# zerod.net
KiCad netlist of a schematic drawn in EAGLE
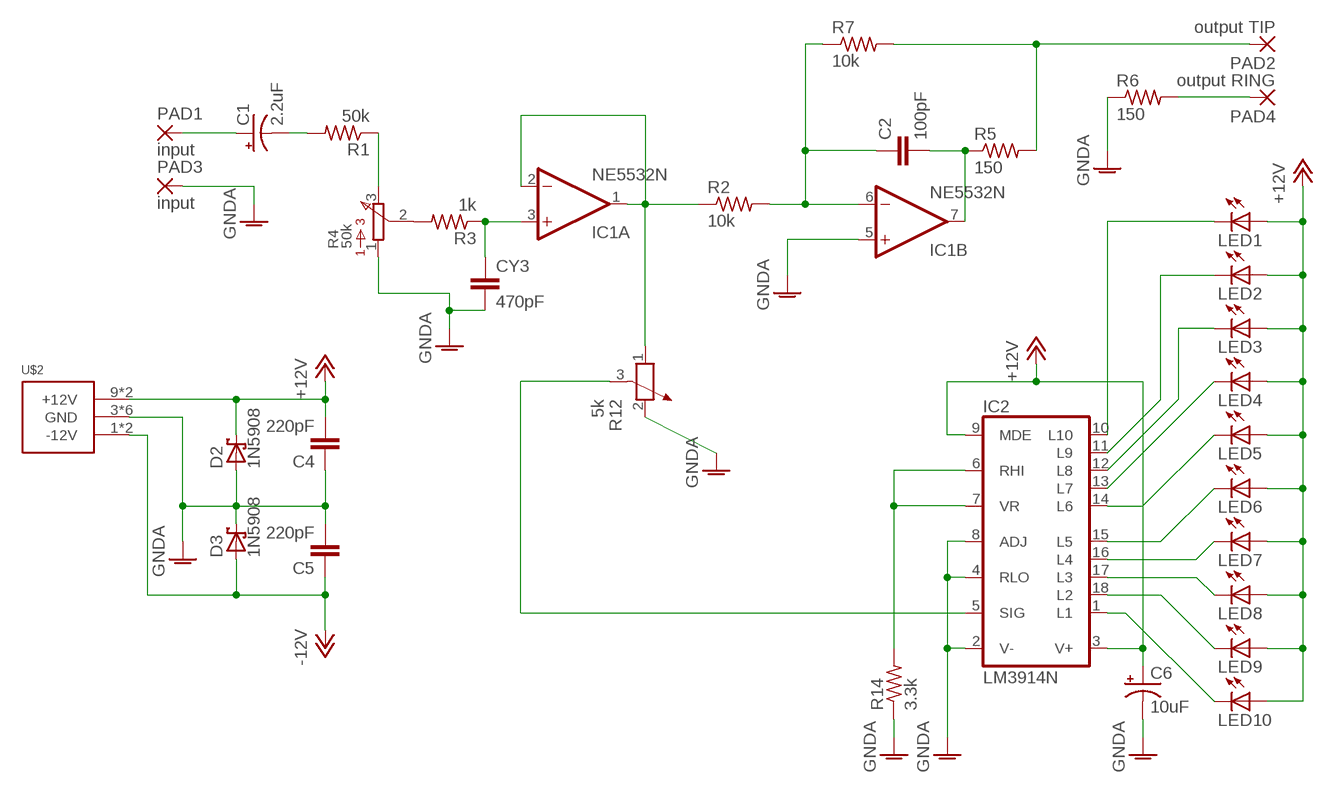
[diagram p0: schematic, sheet 1]

(export (version "E")
  (design (tool "Eeschema 10.0.6"))
  (components
    (comp (ref "C1")
      (value "2.2uF")
      (footprint "eagle-import:E15-6")
      (libsource (lib "eagle-import") (part "CPOL-USE15-6AXIAL"))
    )
    (comp (ref "C2")
      (value "100pF")
      (footprint "eagle-import:C2.5-6")
      (libsource (lib "eagle-import") (part "C2.5/6"))
    )
    (comp (ref "C4")
      (value "220pF")
      (footprint "eagle-import:C025-024X044")
      (libsource (lib "eagle-import") (part "C-EU025-024X044"))
    )
    (comp (ref "C5")
      (value "220pF")
      (footprint "eagle-import:C025-024X044")
      (libsource (lib "eagle-import") (part "C-EU025-024X044"))
    )
    (comp (ref "C6")
      (value "10uF")
      (footprint "eagle-import:E1,8-4")
      (libsource (lib "eagle-import") (part "CPOL-USE1.8-4"))
    )
    (comp (ref "CY3")
      (value "470pF")
      (footprint "eagle-import:YC7B5")
      (libsource (lib "eagle-import") (part "CYYC7B5"))
    )
    (comp (ref "D2")
      (value "1N5908")
      (footprint "eagle-import:C4111-15")
      (libsource (lib "eagle-import") (part "1N5908"))
    )
    (comp (ref "D3")
      (value "1N5908")
      (footprint "eagle-import:C4111-15")
      (libsource (lib "eagle-import") (part "1N5908"))
    )
    (comp (ref "IC1")
      (value "NE5532N")
      (footprint "eagle-import:DIL08")
      (libsource (lib "eagle-import") (part "NE5532N"))
    )
    (comp (ref "IC2")
      (value "LM3914N")
      (footprint "eagle-import:DIL18")
      (libsource (lib "eagle-import") (part "LM3914N"))
    )
    (comp (ref "LED1")
      (value "LED5MM")
      (footprint "eagle-import:LED5MM")
      (libsource (lib "eagle-import") (part "LED5MM"))
    )
    (comp (ref "LED2")
      (value "LED5MM")
      (footprint "eagle-import:LED5MM")
      (libsource (lib "eagle-import") (part "LED5MM"))
    )
    (comp (ref "LED3")
      (value "LED5MM")
      (footprint "eagle-import:LED5MM")
      (libsource (lib "eagle-import") (part "LED5MM"))
    )
    (comp (ref "LED4")
      (value "LED5MM")
      (footprint "eagle-import:LED5MM")
      (libsource (lib "eagle-import") (part "LED5MM"))
    )
    (comp (ref "LED5")
      (value "LED5MM")
      (footprint "eagle-import:LED5MM")
      (libsource (lib "eagle-import") (part "LED5MM"))
    )
    (comp (ref "LED6")
      (value "LED5MM")
      (footprint "eagle-import:LED5MM")
      (libsource (lib "eagle-import") (part "LED5MM"))
    )
    (comp (ref "LED7")
      (value "LED5MM")
      (footprint "eagle-import:LED5MM")
      (libsource (lib "eagle-import") (part "LED5MM"))
    )
    (comp (ref "LED8")
      (value "LED5MM")
      (footprint "eagle-import:LED5MM")
      (libsource (lib "eagle-import") (part "LED5MM"))
    )
    (comp (ref "LED9")
      (value "LED5MM")
      (footprint "eagle-import:LED5MM")
      (libsource (lib "eagle-import") (part "LED5MM"))
    )
    (comp (ref "LED10")
      (value "LED5MM")
      (footprint "eagle-import:LED5MM")
      (libsource (lib "eagle-import") (part "LED5MM"))
    )
    (comp (ref "PAD1")
      (value "input")
      (footprint "eagle-import:3,17_1,3")
      (libsource (lib "eagle-import") (part "3,17/1,3"))
    )
    (comp (ref "PAD2")
      (value "output TIP")
      (footprint "eagle-import:3,17_1,3")
      (libsource (lib "eagle-import") (part "3,17/1,3"))
    )
    (comp (ref "PAD3")
      (value "input")
      (footprint "eagle-import:3,17_1,3")
      (libsource (lib "eagle-import") (part "3,17/1,3"))
    )
    (comp (ref "PAD4")
      (value "output RING")
      (footprint "eagle-import:3,17_1,3")
      (libsource (lib "eagle-import") (part "3,17/1,3"))
    )
    (comp (ref "R1")
      (value "50k")
      (footprint "eagle-import:0207_10")
      (libsource (lib "eagle-import") (part "R-US_0207/10"))
    )
    (comp (ref "R2")
      (value "10k")
      (footprint "eagle-import:0207_10")
      (libsource (lib "eagle-import") (part "R-US_0207/10"))
    )
    (comp (ref "R3")
      (value "1k")
      (footprint "eagle-import:0207_10")
      (libsource (lib "eagle-import") (part "R-US_0207/10"))
    )
    (comp (ref "R4") (value "50k") (footprint "eagle-import:91") (libsource (lib "eagle-import") (part "91")))
    (comp (ref "R5")
      (value "150")
      (footprint "eagle-import:0207_10")
      (libsource (lib "eagle-import") (part "R-US_0207/10"))
    )
    (comp (ref "R6")
      (value "150")
      (footprint "eagle-import:0207_10")
      (libsource (lib "eagle-import") (part "R-US_0207/10"))
    )
    (comp (ref "R7")
      (value "10k")
      (footprint "eagle-import:0207_10")
      (libsource (lib "eagle-import") (part "R-US_0207/10"))
    )
    (comp (ref "R12")
      (value "5k")
      (footprint "eagle-import:PT-10S")
      (libsource (lib "eagle-import") (part "POTENTIOMETER_PT-10S"))
    )
    (comp (ref "R14")
      (value "3.3k")
      (footprint "eagle-import:0207_10")
      (libsource (lib "eagle-import") (part "R-US_0207/10"))
    )
    (comp (ref "U$2")
      (value "POWER_SIMPLE10")
      (footprint "eagle-import:POWER_10")
      (libsource (lib "eagle-import") (part "POWER_SIMPLE10"))
    )
  )
  (nets
    (net (code "1") (name "+12V") (class "Default")
      (node (ref "C4") (pin "2") (pinfunction "2_2") (pintype "passive"))
      (node (ref "C6") (pin "+") (pinfunction "+_+") (pintype "passive"))
      (node (ref "D2") (pin "C") (pinfunction "C_C") (pintype "passive"))
      (node (ref "IC2") (pin "3") (pinfunction "V+_3") (pintype "power_in"))
      (node (ref "IC2") (pin "9") (pinfunction "MDE_9") (pintype "input"))
      (node (ref "LED1") (pin "A") (pinfunction "A_A") (pintype "passive"))
      (node (ref "LED10") (pin "A") (pinfunction "A_A") (pintype "passive"))
      (node (ref "LED2") (pin "A") (pinfunction "A_A") (pintype "passive"))
      (node (ref "LED3") (pin "A") (pinfunction "A_A") (pintype "passive"))
      (node (ref "LED4") (pin "A") (pinfunction "A_A") (pintype "passive"))
      (node (ref "LED5") (pin "A") (pinfunction "A_A") (pintype "passive"))
      (node (ref "LED6") (pin "A") (pinfunction "A_A") (pintype "passive"))
      (node (ref "LED7") (pin "A") (pinfunction "A_A") (pintype "passive"))
      (node (ref "LED8") (pin "A") (pinfunction "A_A") (pintype "passive"))
      (node (ref "LED9") (pin "A") (pinfunction "A_A") (pintype "passive"))
      (node (ref "U$2") (pin "10") (pinfunction "+12V_10") (pintype "bidirectional"))
      (node (ref "U$2") (pin "9") (pinfunction "+12V_9") (pintype "bidirectional"))
    )
    (net (code "2") (name "-12V") (class "Default")
      (node (ref "C5") (pin "1") (pinfunction "1_1") (pintype "passive"))
      (node (ref "D3") (pin "A") (pinfunction "A_A") (pintype "passive"))
      (node (ref "U$2") (pin "1") (pinfunction "-12V_1") (pintype "bidirectional"))
      (node (ref "U$2") (pin "2") (pinfunction "-12V_2") (pintype "bidirectional"))
    )
    (net (code "3") (name "GNDA") (class "Default")
      (node (ref "C4") (pin "1") (pinfunction "1_1") (pintype "passive"))
      (node (ref "C5") (pin "2") (pinfunction "2_2") (pintype "passive"))
      (node (ref "C6") (pin "-") (pinfunction "-_-") (pintype "passive"))
      (node (ref "CY3") (pin "2") (pinfunction "2_2") (pintype "passive"))
      (node (ref "D2") (pin "A") (pinfunction "A_A") (pintype "passive"))
      (node (ref "D3") (pin "C") (pinfunction "C_C") (pintype "passive"))
      (node (ref "IC1") (pin "5") (pinfunction "+IN_5") (pintype "input"))
      (node (ref "IC2") (pin "2") (pinfunction "V-_2") (pintype "power_in"))
      (node (ref "IC2") (pin "4") (pinfunction "RLO_4") (pintype "input"))
      (node (ref "IC2") (pin "8") (pinfunction "ADJ_8") (pintype "input"))
      (node (ref "PAD3") (pin "1") (pinfunction "P_1") (pintype "passive"))
      (node (ref "R12") (pin "2") (pinfunction "2_2") (pintype "passive"))
      (node (ref "R14") (pin "1") (pinfunction "1_1") (pintype "passive"))
      (node (ref "R4") (pin "1") (pinfunction "1_1") (pintype "passive"))
      (node (ref "R6") (pin "1") (pinfunction "1_1") (pintype "passive"))
      (node (ref "U$2") (pin "3") (pinfunction "GND_3") (pintype "bidirectional"))
      (node (ref "U$2") (pin "4") (pinfunction "GND_4") (pintype "bidirectional"))
      (node (ref "U$2") (pin "5") (pinfunction "GND_5") (pintype "bidirectional"))
      (node (ref "U$2") (pin "6") (pinfunction "GND_6") (pintype "bidirectional"))
      (node (ref "U$2") (pin "7") (pinfunction "GND_7") (pintype "bidirectional"))
      (node (ref "U$2") (pin "8") (pinfunction "GND_8") (pintype "bidirectional"))
    )
    (net (code "4") (name "Net-(C1-Pad-)") (class "Default")
      (node (ref "C1") (pin "-") (pinfunction "-_-") (pintype "passive"))
      (node (ref "R1") (pin "2") (pinfunction "2_2") (pintype "passive"))
    )
    (net (code "5") (name "Net-(IC1A-+IN)") (class "Default")
      (node (ref "CY3") (pin "1") (pinfunction "1_1") (pintype "passive"))
      (node (ref "IC1") (pin "3") (pinfunction "+IN_3") (pintype "input"))
      (node (ref "R3") (pin "1") (pinfunction "1_1") (pintype "passive"))
    )
    (net (code "6") (name "Net-(IC1A--IN)") (class "Default")
      (node (ref "IC1") (pin "1") (pinfunction "OUT_1") (pintype "output"))
      (node (ref "IC1") (pin "2") (pinfunction "-IN_2") (pintype "input"))
      (node (ref "R12") (pin "1") (pinfunction "1_1") (pintype "passive"))
      (node (ref "R2") (pin "1") (pinfunction "1_1") (pintype "passive"))
    )
    (net (code "7") (name "Net-(IC1B--IN)") (class "Default")
      (node (ref "C2") (pin "1") (pinfunction "1_1") (pintype "passive"))
      (node (ref "IC1") (pin "6") (pinfunction "-IN_6") (pintype "input"))
      (node (ref "R2") (pin "2") (pinfunction "2_2") (pintype "passive"))
      (node (ref "R7") (pin "1") (pinfunction "1_1") (pintype "passive"))
    )
    (net (code "8") (name "Net-(IC1B-OUT)") (class "Default")
      (node (ref "C2") (pin "2") (pinfunction "2_2") (pintype "passive"))
      (node (ref "IC1") (pin "7") (pinfunction "OUT_7") (pintype "output"))
      (node (ref "R5") (pin "1") (pinfunction "1_1") (pintype "passive"))
    )
    (net (code "9") (name "Net-(IC2-L1)") (class "Default")
      (node (ref "IC2") (pin "1") (pinfunction "L1_1") (pintype "output"))
      (node (ref "LED10") (pin "K") (pinfunction "C_K") (pintype "passive"))
    )
    (net (code "10") (name "Net-(IC2-L2)") (class "Default")
      (node (ref "IC2") (pin "18") (pinfunction "L2_18") (pintype "output"))
      (node (ref "LED9") (pin "K") (pinfunction "C_K") (pintype "passive"))
    )
    (net (code "11") (name "Net-(IC2-L3)") (class "Default")
      (node (ref "IC2") (pin "17") (pinfunction "L3_17") (pintype "output"))
      (node (ref "LED8") (pin "K") (pinfunction "C_K") (pintype "passive"))
    )
    (net (code "12") (name "Net-(IC2-L4)") (class "Default")
      (node (ref "IC2") (pin "16") (pinfunction "L4_16") (pintype "output"))
      (node (ref "LED7") (pin "K") (pinfunction "C_K") (pintype "passive"))
    )
    (net (code "13") (name "Net-(IC2-L5)") (class "Default")
      (node (ref "IC2") (pin "15") (pinfunction "L5_15") (pintype "output"))
      (node (ref "LED6") (pin "K") (pinfunction "C_K") (pintype "passive"))
    )
    (net (code "14") (name "Net-(IC2-L6)") (class "Default")
      (node (ref "IC2") (pin "14") (pinfunction "L6_14") (pintype "output"))
      (node (ref "LED5") (pin "K") (pinfunction "C_K") (pintype "passive"))
    )
    (net (code "15") (name "Net-(IC2-L7)") (class "Default")
      (node (ref "IC2") (pin "13") (pinfunction "L7_13") (pintype "output"))
      (node (ref "LED4") (pin "K") (pinfunction "C_K") (pintype "passive"))
    )
    (net (code "16") (name "Net-(IC2-L8)") (class "Default")
      (node (ref "IC2") (pin "12") (pinfunction "L8_12") (pintype "output"))
      (node (ref "LED3") (pin "K") (pinfunction "C_K") (pintype "passive"))
    )
    (net (code "17") (name "Net-(IC2-L9)") (class "Default")
      (node (ref "IC2") (pin "11") (pinfunction "L9_11") (pintype "output"))
      (node (ref "LED2") (pin "K") (pinfunction "C_K") (pintype "passive"))
    )
    (net (code "18") (name "Net-(IC2-L10)") (class "Default")
      (node (ref "IC2") (pin "10") (pinfunction "L10_10") (pintype "output"))
      (node (ref "LED1") (pin "K") (pinfunction "C_K") (pintype "passive"))
    )
    (net (code "19") (name "Net-(IC2-RHI)") (class "Default")
      (node (ref "IC2") (pin "6") (pinfunction "RHI_6") (pintype "input"))
      (node (ref "IC2") (pin "7") (pinfunction "VR_7") (pintype "output"))
      (node (ref "R14") (pin "2") (pinfunction "2_2") (pintype "passive"))
    )
    (net (code "20") (name "Net-(IC2-SIG)") (class "Default")
      (node (ref "IC2") (pin "5") (pinfunction "SIG_5") (pintype "input"))
      (node (ref "R12") (pin "3") (pinfunction "3_3") (pintype "passive"))
    )
    (net (code "21") (name "Net-(PAD1-P)") (class "Default")
      (node (ref "C1") (pin "+") (pinfunction "+_+") (pintype "passive"))
      (node (ref "PAD1") (pin "1") (pinfunction "P_1") (pintype "passive"))
    )
    (net (code "22") (name "Net-(PAD2-P)") (class "Default")
      (node (ref "PAD2") (pin "1") (pinfunction "P_1") (pintype "passive"))
      (node (ref "R5") (pin "2") (pinfunction "2_2") (pintype "passive"))
      (node (ref "R7") (pin "2") (pinfunction "2_2") (pintype "passive"))
    )
    (net (code "23") (name "Net-(PAD4-P)") (class "Default")
      (node (ref "PAD4") (pin "1") (pinfunction "P_1") (pintype "passive"))
      (node (ref "R6") (pin "2") (pinfunction "2_2") (pintype "passive"))
    )
    (net (code "24") (name "Net-(R1-Pad1)") (class "Default")
      (node (ref "R1") (pin "1") (pinfunction "1_1") (pintype "passive"))
      (node (ref "R4") (pin "3") (pinfunction "3_3") (pintype "passive"))
    )
    (net (code "25") (name "Net-(R3-Pad2)") (class "Default")
      (node (ref "R3") (pin "2") (pinfunction "2_2") (pintype "passive"))
      (node (ref "R4") (pin "2") (pinfunction "2_2") (pintype "passive"))
    )
  )
)
